# M8-Eval-Adapter.net
KiCad netlist of a schematic drawn in EAGLE
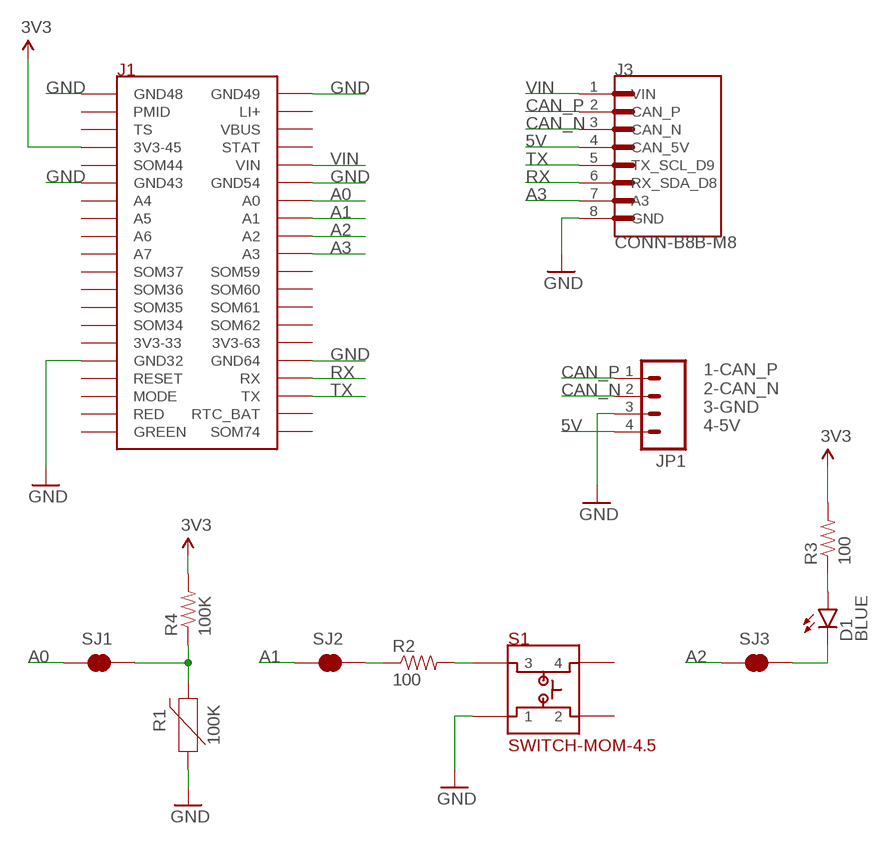
[diagram p0: schematic, sheet 1]

(export (version "E")
  (design (tool "Eeschema 10.0.6"))
  (components
    (comp (ref "D1")
      (value "BLUE")
      (footprint "eagle-import:LED-0603")
      (libsource (lib "eagle-import") (part "LED-BLUE0603"))
    )
    (comp (ref "J1")
      (value "HDR-TRACKER-EVAL-MAIN")
      (footprint "eagle-import:HDR-TRACKER-EVAL-MAIN")
      (libsource (lib "eagle-import") (part "HDR-TRACKER-EVAL-MAIN"))
    )
    (comp (ref "J3")
      (value "CONN-B8B-M8")
      (footprint "eagle-import:JST_B8B-PH-SM4-TB(LF)(SN)")
      (libsource (lib "eagle-import") (part "CONN-B8B-M8"))
    )
    (comp (ref "JP1")
      (value "M04PTH")
      (footprint "eagle-import:1X04")
      (libsource (lib "eagle-import") (part "M04PTH"))
    )
    (comp (ref "R1")
      (value "100K")
      (footprint "eagle-import:0603")
      (libsource (lib "eagle-import") (part "NTC-THERMISTOR-0603"))
    )
    (comp (ref "R2")
      (value "100")
      (footprint "eagle-import:0603-RES")
      (libsource (lib "eagle-import") (part "RES-100-0603.DEV"))
    )
    (comp (ref "R3")
      (value "100")
      (footprint "eagle-import:0603-RES")
      (libsource (lib "eagle-import") (part "RES-100-0603.DEV"))
    )
    (comp (ref "R4")
      (value "100K")
      (footprint "eagle-import:0603-RES")
      (libsource (lib "eagle-import") (part "RES-100K-0603"))
    )
    (comp (ref "S1")
      (value "SWITCH-MOM-4.5")
      (footprint "eagle-import:SWITCH-MOM-4.5")
      (libsource (lib "eagle-import") (part "SWITCH-MOM-4.5"))
    )
    (comp (ref "SJ1")
      (value "JUMPER-PAD-2-NC_BY_TRACENO_SILK")
      (footprint "eagle-import:PAD-JUMPER-2-NC_BY_TRACE_NO_SILK")
      (libsource (lib "eagle-import") (part "JUMPER-PAD-2-NC_BY_TRACENO_SILK"))
    )
    (comp (ref "SJ2")
      (value "JUMPER-PAD-2-NC_BY_TRACENO_SILK")
      (footprint "eagle-import:PAD-JUMPER-2-NC_BY_TRACE_NO_SILK")
      (libsource (lib "eagle-import") (part "JUMPER-PAD-2-NC_BY_TRACENO_SILK"))
    )
    (comp (ref "SJ3")
      (value "JUMPER-PAD-2-NC_BY_TRACENO_SILK")
      (footprint "eagle-import:PAD-JUMPER-2-NC_BY_TRACE_NO_SILK")
      (libsource (lib "eagle-import") (part "JUMPER-PAD-2-NC_BY_TRACENO_SILK"))
    )
  )
  (nets
    (net (code "1") (name "/5V") (class "Default")
      (node (ref "J3") (pin "4") (pinfunction "CAN_5V_4") (pintype "passive"))
      (node (ref "JP1") (pin "4") (pinfunction "4_4") (pintype "passive"))
    )
    (net (code "2") (name "/A0") (class "Default")
      (node (ref "J1") (pin "A0") (pinfunction "A0_A0") (pintype "passive"))
      (node (ref "SJ1") (pin "1") (pinfunction "1_1") (pintype "passive"))
    )
    (net (code "3") (name "/A1") (class "Default")
      (node (ref "J1") (pin "A1") (pinfunction "A1_A1") (pintype "passive"))
      (node (ref "SJ2") (pin "1") (pinfunction "1_1") (pintype "passive"))
    )
    (net (code "4") (name "/A2") (class "Default")
      (node (ref "J1") (pin "A2") (pinfunction "A2_A2") (pintype "passive"))
      (node (ref "SJ3") (pin "1") (pinfunction "1_1") (pintype "passive"))
    )
    (net (code "5") (name "/A3") (class "Default")
      (node (ref "J1") (pin "A3") (pinfunction "A3_A3") (pintype "passive"))
      (node (ref "J3") (pin "7") (pinfunction "A3_7") (pintype "passive"))
    )
    (net (code "6") (name "/CAN_N") (class "Default")
      (node (ref "J3") (pin "3") (pinfunction "CAN_N_3") (pintype "passive"))
      (node (ref "JP1") (pin "2") (pinfunction "2_2") (pintype "passive"))
    )
    (net (code "7") (name "/CAN_P") (class "Default")
      (node (ref "J3") (pin "2") (pinfunction "CAN_P_2") (pintype "passive"))
      (node (ref "JP1") (pin "1") (pinfunction "1_1") (pintype "passive"))
    )
    (net (code "8") (name "/RX") (class "Default")
      (node (ref "J1") (pin "RX") (pinfunction "RX_RX") (pintype "passive"))
      (node (ref "J3") (pin "6") (pinfunction "RX_SDA_D8_6") (pintype "passive"))
    )
    (net (code "9") (name "/TX") (class "Default")
      (node (ref "J1") (pin "TX") (pinfunction "TX_TX") (pintype "passive"))
      (node (ref "J3") (pin "5") (pinfunction "TX_SCL_D9_5") (pintype "passive"))
    )
    (net (code "10") (name "/VIN") (class "Default")
      (node (ref "J1") (pin "VIN") (pinfunction "VIN_VIN") (pintype "passive"))
      (node (ref "J3") (pin "1") (pinfunction "VIN_1") (pintype "passive"))
    )
    (net (code "11") (name "3V3") (class "Default")
      (node (ref "J1") (pin "3V3-45") (pinfunction "3V3-45_3V3-45") (pintype "passive"))
      (node (ref "R3") (pin "2") (pinfunction "2_2") (pintype "passive"))
      (node (ref "R4") (pin "2") (pinfunction "2_2") (pintype "passive"))
    )
    (net (code "12") (name "GND") (class "Default")
      (node (ref "J1") (pin "GND32") (pinfunction "GND32_GND32") (pintype "passive"))
      (node (ref "J1") (pin "GND43") (pinfunction "GND43_GND43") (pintype "passive"))
      (node (ref "J1") (pin "GND48") (pinfunction "GND48_GND48") (pintype "passive"))
      (node (ref "J1") (pin "GND49") (pinfunction "GND49_GND49") (pintype "passive"))
      (node (ref "J1") (pin "GND54") (pinfunction "GND54_GND54") (pintype "passive"))
      (node (ref "J1") (pin "GND64") (pinfunction "GND64_GND64") (pintype "passive"))
      (node (ref "J3") (pin "8") (pinfunction "GND_8") (pintype "passive"))
      (node (ref "JP1") (pin "3") (pinfunction "3_3") (pintype "passive"))
      (node (ref "R1") (pin "1") (pinfunction "1_1") (pintype "bidirectional"))
      (node (ref "S1") (pin "1") (pinfunction "1_1") (pintype "passive"))
    )
    (net (code "13") (name "Net-(D1-PadA)") (class "Default")
      (node (ref "D1") (pin "A") (pinfunction "A_A") (pintype "passive"))
      (node (ref "R3") (pin "1") (pinfunction "1_1") (pintype "passive"))
    )
    (net (code "14") (name "Net-(D1-PadC)") (class "Default")
      (node (ref "D1") (pin "C") (pinfunction "C_C") (pintype "passive"))
      (node (ref "SJ3") (pin "2") (pinfunction "2_2") (pintype "passive"))
    )
    (net (code "15") (name "Net-(R1-Pad2)") (class "Default")
      (node (ref "R1") (pin "2") (pinfunction "2_2") (pintype "bidirectional"))
      (node (ref "R4") (pin "1") (pinfunction "1_1") (pintype "passive"))
      (node (ref "SJ1") (pin "2") (pinfunction "2_2") (pintype "passive"))
    )
    (net (code "16") (name "Net-(R2-Pad1)") (class "Default")
      (node (ref "R2") (pin "1") (pinfunction "1_1") (pintype "passive"))
      (node (ref "SJ2") (pin "2") (pinfunction "2_2") (pintype "passive"))
    )
    (net (code "17") (name "Net-(R2-Pad2)") (class "Default")
      (node (ref "R2") (pin "2") (pinfunction "2_2") (pintype "passive"))
      (node (ref "S1") (pin "3") (pinfunction "3_3") (pintype "passive"))
    )
    (net (code "18") (name "unconnected-(J1-Pad3V3-33)") (class "Default")
      (node (ref "J1") (pin "3V3-33") (pinfunction "3V3-33_3V3-33") (pintype "passive"))
    )
    (net (code "19") (name "unconnected-(J1-Pad3V3-63)") (class "Default")
      (node (ref "J1") (pin "3V3-63") (pinfunction "3V3-63_3V3-63") (pintype "passive"))
    )
    (net (code "20") (name "unconnected-(J1-PadA4)") (class "Default")
      (node (ref "J1") (pin "A4") (pinfunction "A4_A4") (pintype "passive"))
    )
    (net (code "21") (name "unconnected-(J1-PadA5)") (class "Default")
      (node (ref "J1") (pin "A5") (pinfunction "A5_A5") (pintype "passive"))
    )
    (net (code "22") (name "unconnected-(J1-PadA6)") (class "Default")
      (node (ref "J1") (pin "A6") (pinfunction "A6_A6") (pintype "passive"))
    )
    (net (code "23") (name "unconnected-(J1-PadA7)") (class "Default")
      (node (ref "J1") (pin "A7") (pinfunction "A7_A7") (pintype "passive"))
    )
    (net (code "24") (name "unconnected-(J1-PadGREEN)") (class "Default")
      (node (ref "J1") (pin "GREEN") (pinfunction "GREEN_GREEN") (pintype "passive"))
    )
    (net (code "25") (name "unconnected-(J1-PadLI+)") (class "Default")
      (node (ref "J1") (pin "LI+") (pinfunction "LI+_LI+") (pintype "passive"))
    )
    (net (code "26") (name "unconnected-(J1-PadMODE)") (class "Default")
      (node (ref "J1") (pin "MODE") (pinfunction "MODE_MODE") (pintype "passive"))
    )
    (net (code "27") (name "unconnected-(J1-PadPMID)") (class "Default")
      (node (ref "J1") (pin "PMID") (pinfunction "PMID_PMID") (pintype "passive"))
    )
    (net (code "28") (name "unconnected-(J1-PadRED)") (class "Default")
      (node (ref "J1") (pin "RED") (pinfunction "RED_RED") (pintype "passive"))
    )
    (net (code "29") (name "unconnected-(J1-PadRESET)") (class "Default")
      (node (ref "J1") (pin "RESET") (pinfunction "RESET_RESET") (pintype "passive"))
    )
    (net (code "30") (name "unconnected-(J1-PadRTC_BAT)") (class "Default")
      (node (ref "J1") (pin "RTC_BAT") (pinfunction "RTC_BAT_RTC_BAT") (pintype "passive"))
    )
    (net (code "31") (name "unconnected-(J1-PadSOM34)") (class "Default")
      (node (ref "J1") (pin "SOM34") (pinfunction "SOM34_SOM34") (pintype "passive"))
    )
    (net (code "32") (name "unconnected-(J1-PadSOM35)") (class "Default")
      (node (ref "J1") (pin "SOM35") (pinfunction "SOM35_SOM35") (pintype "passive"))
    )
    (net (code "33") (name "unconnected-(J1-PadSOM36)") (class "Default")
      (node (ref "J1") (pin "SOM36") (pinfunction "SOM36_SOM36") (pintype "passive"))
    )
    (net (code "34") (name "unconnected-(J1-PadSOM37)") (class "Default")
      (node (ref "J1") (pin "SOM37") (pinfunction "SOM37_SOM37") (pintype "passive"))
    )
    (net (code "35") (name "unconnected-(J1-PadSOM44)") (class "Default")
      (node (ref "J1") (pin "SOM44") (pinfunction "SOM44_SOM44") (pintype "passive"))
    )
    (net (code "36") (name "unconnected-(J1-PadSOM59)") (class "Default")
      (node (ref "J1") (pin "SOM59") (pinfunction "SOM59_SOM59") (pintype "passive"))
    )
    (net (code "37") (name "unconnected-(J1-PadSOM60)") (class "Default")
      (node (ref "J1") (pin "SOM60") (pinfunction "SOM60_SOM60") (pintype "passive"))
    )
    (net (code "38") (name "unconnected-(J1-PadSOM61)") (class "Default")
      (node (ref "J1") (pin "SOM61") (pinfunction "SOM61_SOM61") (pintype "passive"))
    )
    (net (code "39") (name "unconnected-(J1-PadSOM62)") (class "Default")
      (node (ref "J1") (pin "SOM62") (pinfunction "SOM62_SOM62") (pintype "passive"))
    )
    (net (code "40") (name "unconnected-(J1-PadSTAT)") (class "Default")
      (node (ref "J1") (pin "STAT") (pinfunction "STAT_STAT") (pintype "passive"))
    )
    (net (code "41") (name "unconnected-(J1-PadTS)") (class "Default")
      (node (ref "J1") (pin "TS") (pinfunction "TS_TS") (pintype "passive"))
    )
    (net (code "42") (name "unconnected-(J1-PadVBUS)") (class "Default")
      (node (ref "J1") (pin "VBUS") (pinfunction "VBUS_VBUS") (pintype "passive"))
    )
    (net (code "43") (name "unconnected-(J1-SOM74-PadSOM75)") (class "Default")
      (node (ref "J1") (pin "SOM75") (pinfunction "SOM74_SOM75") (pintype "passive"))
    )
    (net (code "44") (name "unconnected-(S1-Pad2)") (class "Default")
      (node (ref "S1") (pin "2") (pinfunction "2_2") (pintype "passive"))
    )
    (net (code "45") (name "unconnected-(S1-Pad4)") (class "Default")
      (node (ref "S1") (pin "4") (pinfunction "4_4") (pintype "passive"))
    )
  )
)
